# red_glow.net
KiCad netlist of a schematic drawn in EAGLE
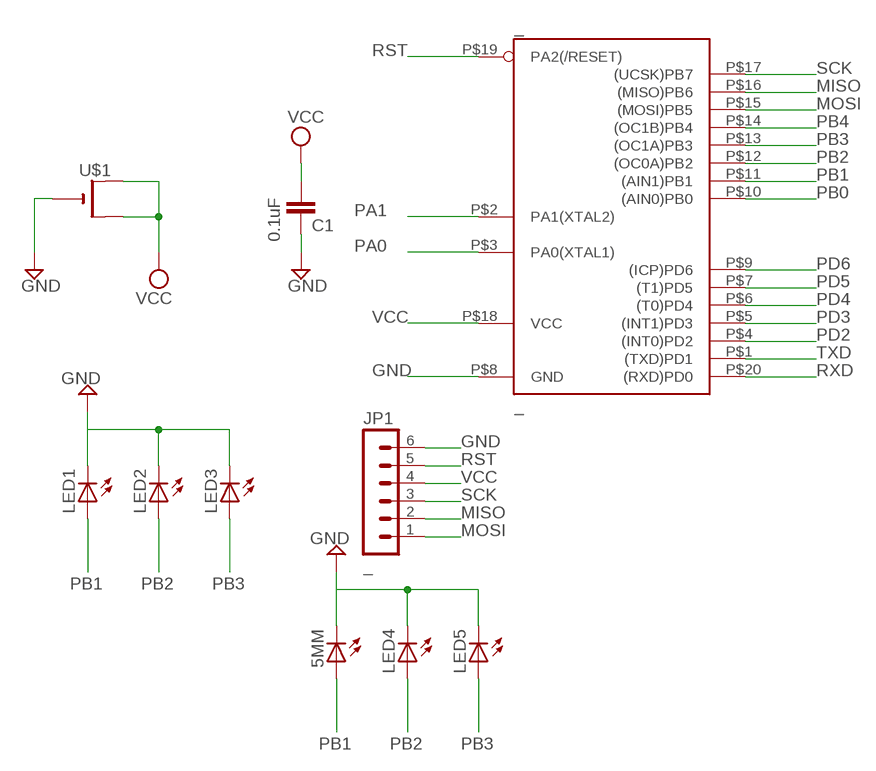
[diagram p0: schematic, sheet 1]

(export (version "E")
  (design (tool "Eeschema 10.0.6"))
  (components
    (comp (ref "5MM")
      (value "LED5MM")
      (footprint "eagle-import:LED5MM")
      (libsource (lib "eagle-import") (part "adafruit_LED5MM"))
    )
    (comp (ref "C1")
      (value "0.1uF")
      (footprint "eagle-import:0805")
      (libsource (lib "eagle-import") (part "CAP0805"))
    )
    (comp (ref "JP1")
      (value "_")
      (footprint "eagle-import:MA06-1")
      (libsource (lib "eagle-import") (part "MA06-1"))
    )
    (comp (ref "LED1")
      (value "LED1206")
      (footprint "eagle-import:LED-1206")
      (libsource (lib "eagle-import") (part "LED1206"))
    )
    (comp (ref "LED2")
      (value "LED1206")
      (footprint "eagle-import:LED-1206")
      (libsource (lib "eagle-import") (part "LED1206"))
    )
    (comp (ref "LED3")
      (value "LED1206")
      (footprint "eagle-import:LED-1206")
      (libsource (lib "eagle-import") (part "LED1206"))
    )
    (comp (ref "LED4")
      (value "LED5MM")
      (footprint "eagle-import:LED5MM")
      (libsource (lib "eagle-import") (part "adafruit_LED5MM"))
    )
    (comp (ref "LED5")
      (value "LED5MM")
      (footprint "eagle-import:LED5MM")
      (libsource (lib "eagle-import") (part "adafruit_LED5MM"))
    )
    (comp (ref "U$1")
      (value "CR2032SMT")
      (footprint "eagle-import:CR2032-SMD")
      (libsource (lib "eagle-import") (part "CR2032SMT"))
    )
    (comp (ref "_")
      (value "_")
      (footprint "eagle-import:MLF20")
      (libsource (lib "eagle-import") (part "TINY2313-M"))
    )
  )
  (nets
    (net (code "1") (name "/MISO") (class "Default")
      (node (ref "JP1") (pin "2") (pinfunction "2_2") (pintype "passive"))
      (node (ref "_") (pin "P$16") (pinfunction "(MISO)PB6_P$16") (pintype "bidirectional"))
    )
    (net (code "2") (name "/MOSI") (class "Default")
      (node (ref "JP1") (pin "1") (pinfunction "1_1") (pintype "passive"))
      (node (ref "_") (pin "P$15") (pinfunction "(MOSI)PB5_P$15") (pintype "bidirectional"))
    )
    (net (code "3") (name "/PA0") (class "Default")
      (node (ref "_") (pin "P$3") (pinfunction "PA0(XTAL1)_P$3") (pintype "bidirectional"))
    )
    (net (code "4") (name "/PA1") (class "Default")
      (node (ref "_") (pin "P$2") (pinfunction "PA1(XTAL2)_P$2") (pintype "bidirectional"))
    )
    (net (code "5") (name "/PB0") (class "Default")
      (node (ref "_") (pin "P$10") (pinfunction "(AIN0)PB0_P$10") (pintype "bidirectional"))
    )
    (net (code "6") (name "/PB1") (class "Default")
      (node (ref "5MM") (pin "A") (pinfunction "A_A") (pintype "passive"))
      (node (ref "LED1") (pin "A") (pinfunction "A_A") (pintype "passive"))
      (node (ref "_") (pin "P$11") (pinfunction "(AIN1)PB1_P$11") (pintype "bidirectional"))
    )
    (net (code "7") (name "/PB2") (class "Default")
      (node (ref "LED2") (pin "A") (pinfunction "A_A") (pintype "passive"))
      (node (ref "LED4") (pin "A") (pinfunction "A_A") (pintype "passive"))
      (node (ref "_") (pin "P$12") (pinfunction "(OC0A)PB2_P$12") (pintype "bidirectional"))
    )
    (net (code "8") (name "/PB3") (class "Default")
      (node (ref "LED3") (pin "A") (pinfunction "A_A") (pintype "passive"))
      (node (ref "LED5") (pin "A") (pinfunction "A_A") (pintype "passive"))
      (node (ref "_") (pin "P$13") (pinfunction "(OC1A)PB3_P$13") (pintype "bidirectional"))
    )
    (net (code "9") (name "/PB4") (class "Default")
      (node (ref "_") (pin "P$14") (pinfunction "(OC1B)PB4_P$14") (pintype "bidirectional"))
    )
    (net (code "10") (name "/PD2") (class "Default")
      (node (ref "_") (pin "P$4") (pinfunction "(INT0)PD2_P$4") (pintype "bidirectional"))
    )
    (net (code "11") (name "/PD3") (class "Default")
      (node (ref "_") (pin "P$5") (pinfunction "(INT1)PD3_P$5") (pintype "bidirectional"))
    )
    (net (code "12") (name "/PD4") (class "Default")
      (node (ref "_") (pin "P$6") (pinfunction "(T0)PD4_P$6") (pintype "bidirectional"))
    )
    (net (code "13") (name "/PD5") (class "Default")
      (node (ref "_") (pin "P$7") (pinfunction "(T1)PD5_P$7") (pintype "bidirectional"))
    )
    (net (code "14") (name "/PD6") (class "Default")
      (node (ref "_") (pin "P$9") (pinfunction "(ICP)PD6_P$9") (pintype "bidirectional"))
    )
    (net (code "15") (name "/RST") (class "Default")
      (node (ref "JP1") (pin "5") (pinfunction "5_5") (pintype "passive"))
      (node (ref "_") (pin "P$19") (pinfunction "PA2(/RESET)_P$19") (pintype "input"))
    )
    (net (code "16") (name "/RXD") (class "Default")
      (node (ref "_") (pin "P$20") (pinfunction "(RXD)PD0_P$20") (pintype "bidirectional"))
    )
    (net (code "17") (name "/SCK") (class "Default")
      (node (ref "JP1") (pin "3") (pinfunction "3_3") (pintype "passive"))
      (node (ref "_") (pin "P$17") (pinfunction "(UCSK)PB7_P$17") (pintype "bidirectional"))
    )
    (net (code "18") (name "/TXD") (class "Default")
      (node (ref "_") (pin "P$1") (pinfunction "(TXD)PD1_P$1") (pintype "bidirectional"))
    )
    (net (code "19") (name "GND") (class "Default")
      (node (ref "5MM") (pin "K") (pinfunction "C_K") (pintype "passive"))
      (node (ref "C1") (pin "2") (pinfunction "2_2") (pintype "passive"))
      (node (ref "JP1") (pin "6") (pinfunction "6_6") (pintype "passive"))
      (node (ref "LED1") (pin "C") (pinfunction "C_C") (pintype "passive"))
      (node (ref "LED2") (pin "C") (pinfunction "C_C") (pintype "passive"))
      (node (ref "LED3") (pin "C") (pinfunction "C_C") (pintype "passive"))
      (node (ref "LED4") (pin "K") (pinfunction "C_K") (pintype "passive"))
      (node (ref "LED5") (pin "K") (pinfunction "C_K") (pintype "passive"))
      (node (ref "U$1") (pin "-") (pinfunction "-_-") (pintype "passive"))
      (node (ref "_") (pin "P$8") (pinfunction "GND_P$8") (pintype "power_in"))
    )
    (net (code "20") (name "VCC") (class "Default")
      (node (ref "C1") (pin "1") (pinfunction "1_1") (pintype "passive"))
      (node (ref "JP1") (pin "4") (pinfunction "4_4") (pintype "passive"))
      (node (ref "U$1") (pin "+$1") (pinfunction "+_+$1") (pintype "passive"))
      (node (ref "U$1") (pin "+$2") (pinfunction "+1_+$2") (pintype "passive"))
      (node (ref "_") (pin "P$18") (pinfunction "VCC_P$18") (pintype "power_in"))
    )
  )
)
